# Sheet1.net
KiCad netlist of a schematic drawn in Altium Designer
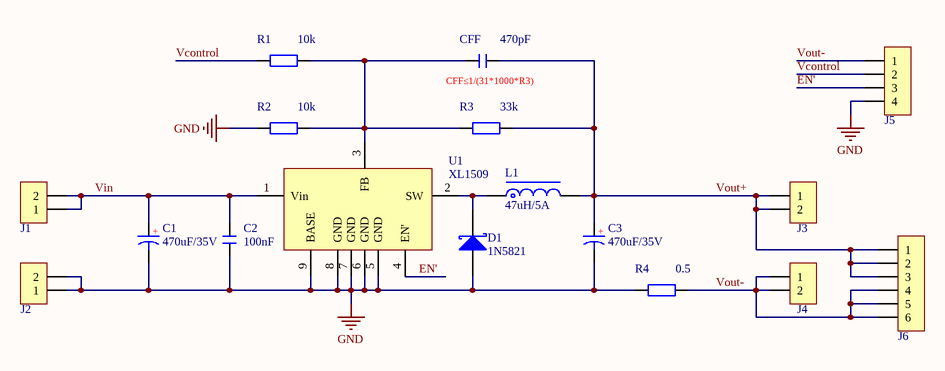
[diagram p0: Sheet1.SchDoc]

(export (version "E")
  (design (tool "Eeschema 10.0.6"))
  (components
    (comp (ref "C1")
      (value "470uF/35V")
      (footprint "CS 10*8 - B")
      (description "贴片固态电容")
      (fields (field (name "版权归属") "封装库来自淘宝 ID：黄晶宝石"))
      (libsource (lib "0.1 - 电阻-电容-电感") (part "CS_SMD"))
    )
    (comp (ref "C2")
      (value "100nF")
      (footprint "C0603_L")
      (description "贴片电容")
      (libsource (lib "0.1 - 电阻-电容-电感") (part "C"))
    )
    (comp (ref "C3")
      (value "470uF/35V")
      (footprint "CS 10*8 - B")
      (description "贴片固态电容")
      (fields (field (name "版权归属") "封装库来自淘宝 ID：黄晶宝石"))
      (libsource (lib "0.1 - 电阻-电容-电感") (part "CS_SMD"))
    )
    (comp (ref "CFF")
      (value "470pF")
      (footprint "C0603_L")
      (description "贴片电容")
      (libsource (lib "0.1 - 电阻-电容-电感") (part "C"))
    )
    (comp (ref "D1") (value "1N5821") (footprint "DO41") (libsource (lib "Schlib1") (part "1N5821")))
    (comp (ref "J1")
      (value "HDR-1X2")
      (footprint "HDR2.54-LI-2P")
      (description "2P接插件")
      (fields (field (name "版权归属") "封装库来自淘宝 ID：黄晶宝石"))
      (libsource (lib "5.4 - 接插件-脚距2.54 (100mil) ") (part "Header 2"))
    )
    (comp (ref "J2")
      (value "HDR-1X2")
      (footprint "HDR2.54-LI-2P")
      (description "2P接插件")
      (fields (field (name "版权归属") "封装库来自淘宝 ID：黄晶宝石"))
      (libsource (lib "5.4 - 接插件-脚距2.54 (100mil) ") (part "Header 2"))
    )
    (comp (ref "J3")
      (value "HDR-1X2")
      (footprint "HDR2.54-LI-2P")
      (description "2P接插件")
      (fields (field (name "版权归属") "封装库来自淘宝 ID：黄晶宝石"))
      (libsource (lib "") (part "Header 2_1"))
    )
    (comp (ref "J4")
      (value "HDR-1X2")
      (footprint "HDR2.54-LI-2P")
      (description "2P接插件")
      (fields (field (name "版权归属") "封装库来自淘宝 ID：黄晶宝石"))
      (libsource (lib "") (part "Header 2_1"))
    )
    (comp (ref "J5")
      (value "HDR-1X4")
      (footprint "HDR2.54-LI-4P")
      (description "4P接插件")
      (fields (field (name "版权归属") "封装库来自淘宝 ID：黄晶宝石"))
      (libsource (lib "5.4 - 接插件-脚距2.54 (100mil) ") (part "Header 4"))
    )
    (comp (ref "J6")
      (value "HDR-1X6")
      (footprint "HDR2.54-M-LI-6P")
      (description "6P接插件")
      (fields (field (name "版权归属") "封装库来自淘宝 ID：黄晶宝石"))
      (libsource (lib "5.4 - 接插件-脚距2.54 (100mil) ") (part "Header 6"))
    )
    (comp (ref "L1")
      (value "47uH/5A")
      (footprint "LMR135")
      (description "功率磁环电感")
      (libsource (lib "0.1 - 电阻-电容-电感") (part "L-MR"))
    )
    (comp (ref "R1")
      (value "10k")
      (footprint "R0603_L")
      (description "贴片电阻")
      (fields (field (name "版权归属") "来自淘宝 ID：黄晶宝石"))
      (libsource (lib "0.1 - 电阻-电容-电感") (part "R"))
    )
    (comp (ref "R2")
      (value "10k")
      (footprint "R0603_L")
      (description "贴片电阻")
      (fields (field (name "版权归属") "来自淘宝 ID：黄晶宝石"))
      (libsource (lib "0.1 - 电阻-电容-电感") (part "R"))
    )
    (comp (ref "R3")
      (value "33k")
      (footprint "R0603_L")
      (description "贴片电阻")
      (fields (field (name "版权归属") "来自淘宝 ID：黄晶宝石"))
      (libsource (lib "0.1 - 电阻-电容-电感") (part "R"))
    )
    (comp (ref "R4")
      (value "0.5")
      (footprint "R1206_L")
      (description "贴片电阻")
      (fields (field (name "版权归属") "来自淘宝 ID：黄晶宝石"))
      (libsource (lib "0.1 - 电阻-电容-电感") (part "R"))
    )
    (comp (ref "U1") (value "XL1509") (footprint "ESOP8_M") (libsource (lib "Schlib1") (part "XL1509")))
  )
  (nets
    (net (code "1") (name "/EN'") (class "Default")
      (node (ref "J5") (pin "3") (pinfunction "3_3") (pintype "passive"))
      (node (ref "U1") (pin "4") (pinfunction "EN'_4") (pintype "passive"))
    )
    (net (code "2") (name "/Vcontrol") (class "Default")
      (node (ref "J5") (pin "2") (pinfunction "2_2") (pintype "passive"))
      (node (ref "R1") (pin "1") (pinfunction "1_1") (pintype "passive"))
    )
    (net (code "3") (name "/Vin") (class "Default")
      (node (ref "C1") (pin "1") (pinfunction "1_1") (pintype "passive"))
      (node (ref "C2") (pin "1") (pinfunction "1_1") (pintype "passive"))
      (node (ref "J1") (pin "1") (pinfunction "1_1") (pintype "passive"))
      (node (ref "J1") (pin "2") (pinfunction "2_2") (pintype "passive"))
      (node (ref "U1") (pin "1") (pinfunction "Vin_1") (pintype "passive"))
    )
    (net (code "4") (name "/Vout+") (class "Default")
      (node (ref "C3") (pin "1") (pinfunction "1_1") (pintype "passive"))
      (node (ref "CFF") (pin "2") (pinfunction "2_2") (pintype "passive"))
      (node (ref "J3") (pin "1") (pinfunction "1_1") (pintype "passive"))
      (node (ref "J3") (pin "2") (pinfunction "2_2") (pintype "passive"))
      (node (ref "J6") (pin "1") (pinfunction "1_1") (pintype "passive"))
      (node (ref "J6") (pin "2") (pinfunction "2_2") (pintype "passive"))
      (node (ref "J6") (pin "3") (pinfunction "3_3") (pintype "passive"))
      (node (ref "L1") (pin "2") (pinfunction "2_2") (pintype "passive"))
      (node (ref "R3") (pin "2") (pinfunction "2_2") (pintype "passive"))
    )
    (net (code "5") (name "/Vout-") (class "Default")
      (node (ref "J4") (pin "1") (pinfunction "1_1") (pintype "passive"))
      (node (ref "J4") (pin "2") (pinfunction "2_2") (pintype "passive"))
      (node (ref "J5") (pin "1") (pinfunction "1_1") (pintype "passive"))
      (node (ref "J6") (pin "4") (pinfunction "4_4") (pintype "passive"))
      (node (ref "J6") (pin "5") (pinfunction "5_5") (pintype "passive"))
      (node (ref "J6") (pin "6") (pinfunction "6_6") (pintype "passive"))
      (node (ref "R4") (pin "2") (pinfunction "2_2") (pintype "passive"))
    )
    (net (code "6") (name "GND") (class "Default")
      (node (ref "C1") (pin "2") (pinfunction "2_2") (pintype "passive"))
      (node (ref "C2") (pin "2") (pinfunction "2_2") (pintype "passive"))
      (node (ref "C3") (pin "2") (pinfunction "2_2") (pintype "passive"))
      (node (ref "D1") (pin "1") (pinfunction "A_1") (pintype "passive"))
      (node (ref "J2") (pin "1") (pinfunction "1_1") (pintype "passive"))
      (node (ref "J2") (pin "2") (pinfunction "2_2") (pintype "passive"))
      (node (ref "J5") (pin "4") (pinfunction "4_4") (pintype "passive"))
      (node (ref "R2") (pin "1") (pinfunction "1_1") (pintype "passive"))
      (node (ref "R4") (pin "1") (pinfunction "1_1") (pintype "passive"))
      (node (ref "U1") (pin "5") (pinfunction "GND_5") (pintype "passive"))
      (node (ref "U1") (pin "6") (pinfunction "GND_6") (pintype "passive"))
      (node (ref "U1") (pin "7") (pinfunction "GND_7") (pintype "passive"))
      (node (ref "U1") (pin "8") (pinfunction "GND_8") (pintype "passive"))
      (node (ref "U1") (pin "9") (pinfunction "BASE_9") (pintype "passive"))
    )
    (net (code "7") (name "Net-(D1-K)") (class "Default")
      (node (ref "D1") (pin "2") (pinfunction "K_2") (pintype "passive"))
      (node (ref "L1") (pin "1") (pinfunction "1_1") (pintype "passive"))
      (node (ref "U1") (pin "2") (pinfunction "SW_2") (pintype "passive"))
    )
    (net (code "8") (name "Net-(U1-FB)") (class "Default")
      (node (ref "CFF") (pin "1") (pinfunction "1_1") (pintype "passive"))
      (node (ref "R1") (pin "2") (pinfunction "2_2") (pintype "passive"))
      (node (ref "R2") (pin "2") (pinfunction "2_2") (pintype "passive"))
      (node (ref "R3") (pin "1") (pinfunction "1_1") (pintype "passive"))
      (node (ref "U1") (pin "3") (pinfunction "FB_3") (pintype "passive"))
    )
  )
)
